# Reefwing-NFC-Card-RevD.net
KiCad netlist of a schematic drawn in EasyEDA
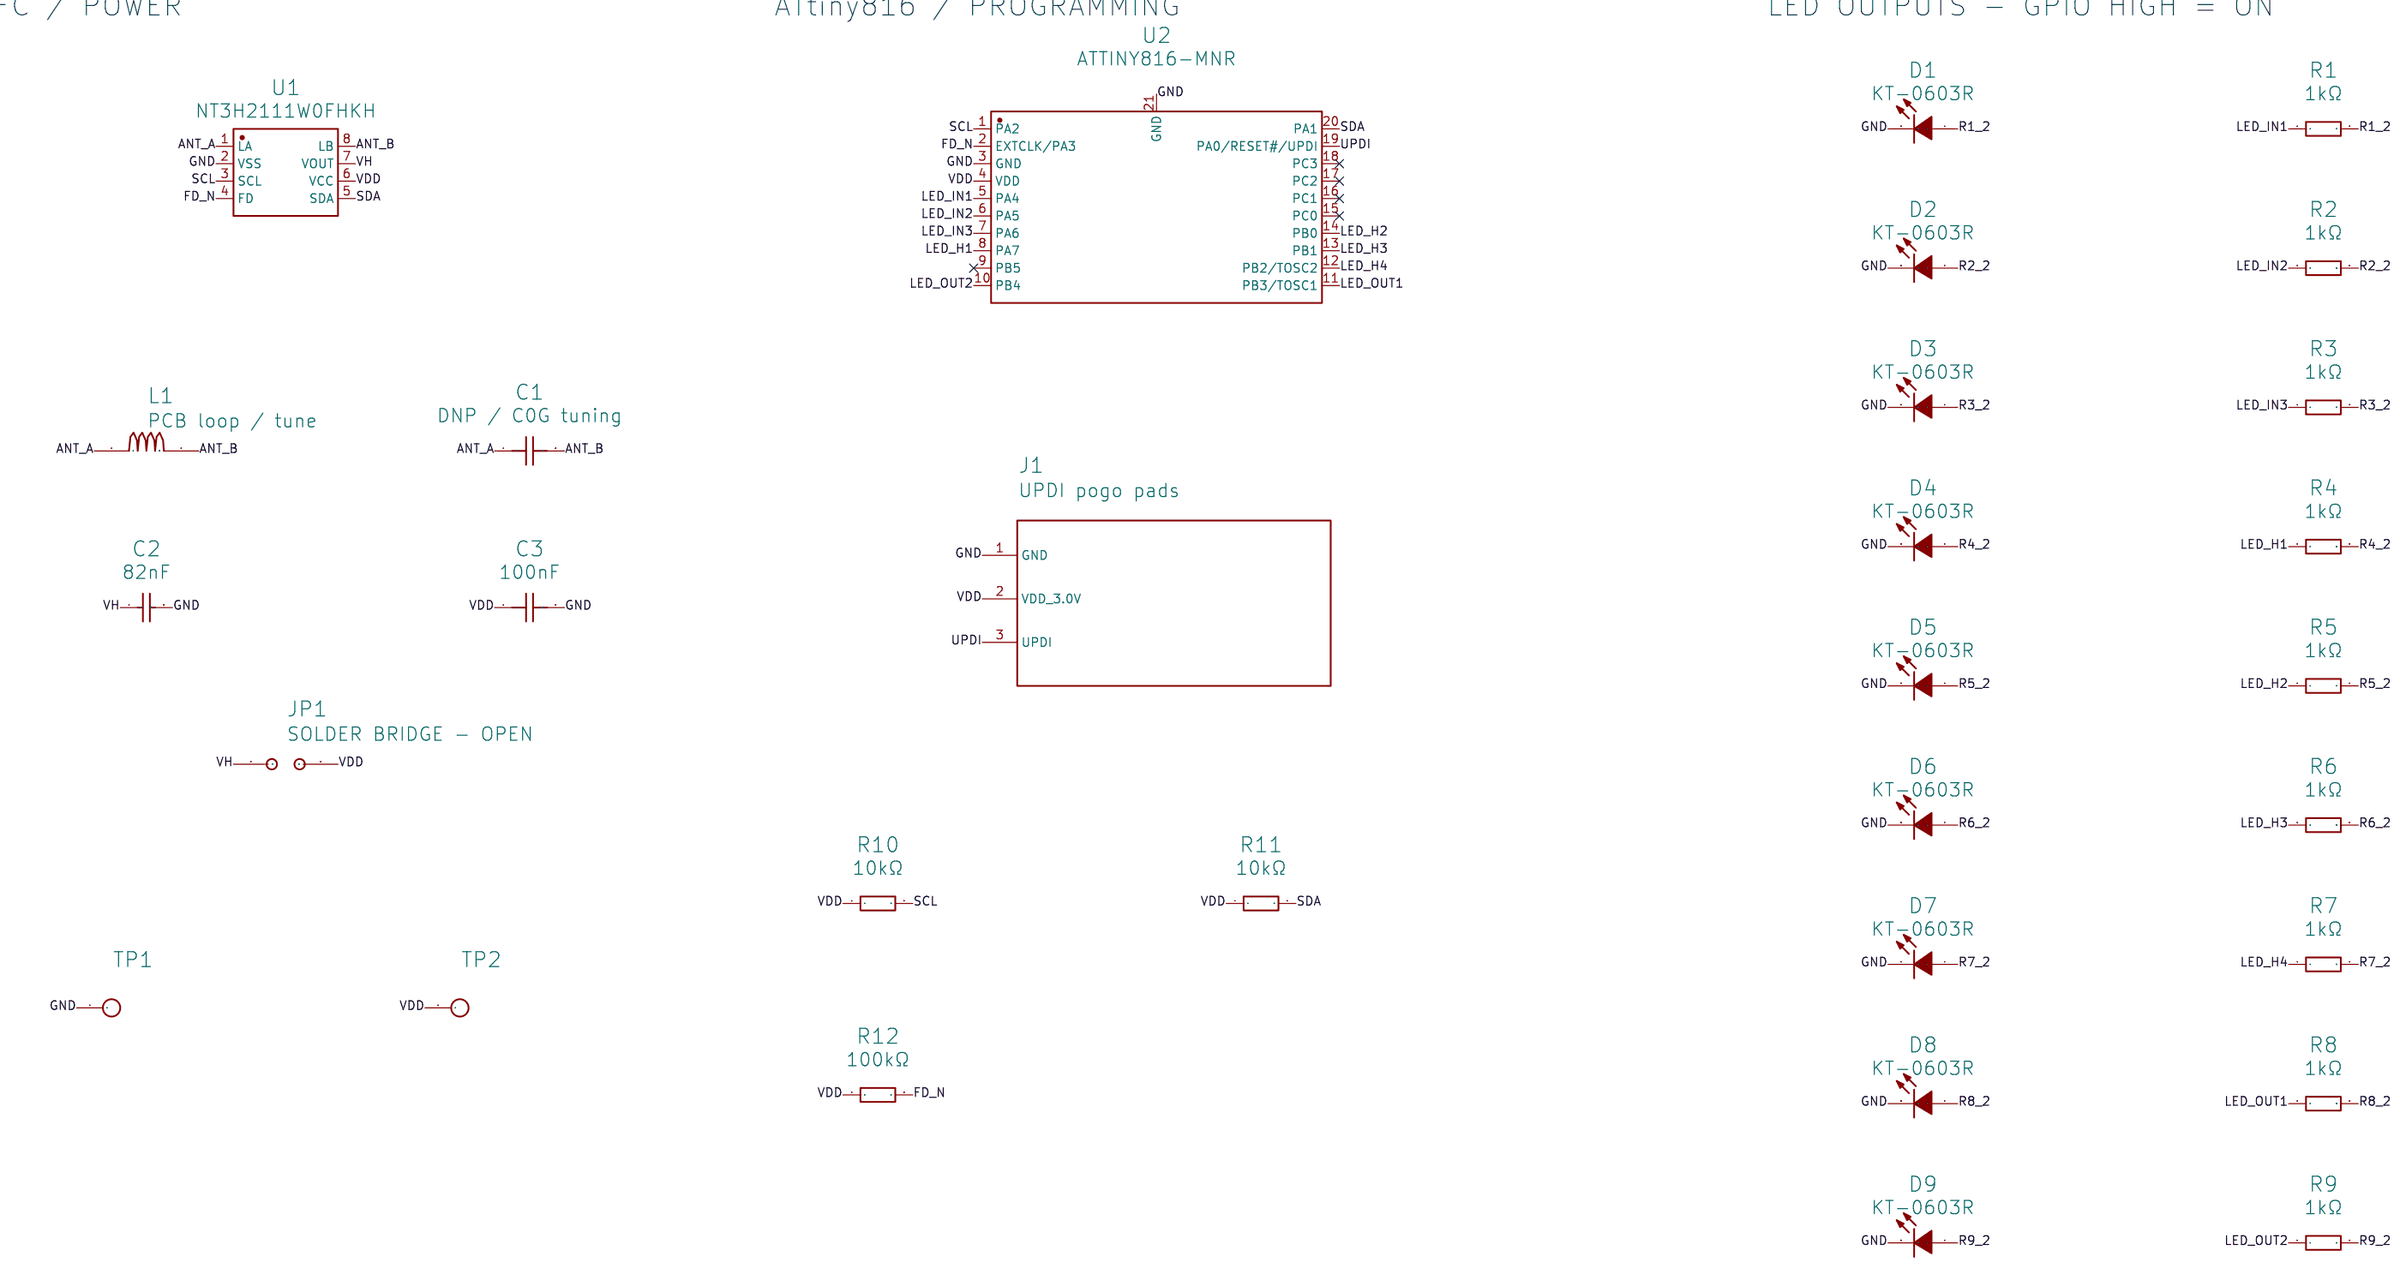
[diagram p0: schematic sheet]

(export (version "E")
  (design (tool "Eeschema 10.0.6"))
  (components
    (comp (ref "C1") (value "DNP / C0G tuning") (libsource (lib "") (part "Unknown_390_370")))
    (comp (ref "C2")
      (value "82nF")
      (fields
        (field (name "Manufacturer Part") "CC0603KRX7R9BB823")
        (field (name "Manufacturer") "YAGEO(国巨)")
      )
      (libsource (lib "") (part "Unknown_170_460"))
    )
    (comp (ref "C3")
      (value "100nF")
      (fields
        (field (name "Manufacturer Part") "CC0603KRX7R9BB104")
        (field (name "Manufacturer") "YAGEO(国巨)")
      )
      (libsource (lib "") (part "Unknown_390_460"))
    )
    (comp (ref "D1")
      (value "KT-0603R")
      (fields (field (name "Manufacturer") "KENTO"))
      (libsource (lib "") (part "Unknown_1190_185"))
    )
    (comp (ref "D2")
      (value "KT-0603R")
      (fields (field (name "Manufacturer") "KENTO"))
      (libsource (lib "") (part "Unknown_1190_265"))
    )
    (comp (ref "D3")
      (value "KT-0603R")
      (fields (field (name "Manufacturer") "KENTO"))
      (libsource (lib "") (part "Unknown_1190_345"))
    )
    (comp (ref "D4")
      (value "KT-0603R")
      (fields (field (name "Manufacturer") "KENTO"))
      (libsource (lib "") (part "Unknown_1190_425"))
    )
    (comp (ref "D5")
      (value "KT-0603R")
      (fields (field (name "Manufacturer") "KENTO"))
      (libsource (lib "") (part "Unknown_1190_505"))
    )
    (comp (ref "D6")
      (value "KT-0603R")
      (fields (field (name "Manufacturer") "KENTO"))
      (libsource (lib "") (part "Unknown_1190_585"))
    )
    (comp (ref "D7")
      (value "KT-0603R")
      (fields (field (name "Manufacturer") "KENTO"))
      (libsource (lib "") (part "Unknown_1190_665"))
    )
    (comp (ref "D8")
      (value "KT-0603R")
      (fields (field (name "Manufacturer") "KENTO"))
      (libsource (lib "") (part "Unknown_1190_745"))
    )
    (comp (ref "D9")
      (value "KT-0603R")
      (fields (field (name "Manufacturer") "KENTO"))
      (libsource (lib "") (part "Unknown_1190_825"))
    )
    (comp (ref "J1") (value "UPDI pogo pads") (libsource (lib "") (part "Unknown_670_410")))
    (comp (ref "JP1") (value "SOLDER BRIDGE - OPEN") (libsource (lib "") (part "Unknown_250_550")))
    (comp (ref "L1") (value "PCB loop / tune") (libsource (lib "") (part "Unknown_170_370")))
    (comp (ref "R1")
      (value "1kΩ")
      (fields
        (field (name "Manufacturer Part") "0603WAF1001T5E")
        (field (name "Manufacturer") "UNI-ROYAL(厚声)")
      )
      (libsource (lib "") (part "Unknown_1420_185"))
    )
    (comp (ref "R2")
      (value "1kΩ")
      (fields
        (field (name "Manufacturer Part") "0603WAF1001T5E")
        (field (name "Manufacturer") "UNI-ROYAL(厚声)")
      )
      (libsource (lib "") (part "Unknown_1420_265"))
    )
    (comp (ref "R3")
      (value "1kΩ")
      (fields
        (field (name "Manufacturer Part") "0603WAF1001T5E")
        (field (name "Manufacturer") "UNI-ROYAL(厚声)")
      )
      (libsource (lib "") (part "Unknown_1420_345"))
    )
    (comp (ref "R4")
      (value "1kΩ")
      (fields
        (field (name "Manufacturer Part") "0603WAF1001T5E")
        (field (name "Manufacturer") "UNI-ROYAL(厚声)")
      )
      (libsource (lib "") (part "Unknown_1420_425"))
    )
    (comp (ref "R5")
      (value "1kΩ")
      (fields
        (field (name "Manufacturer Part") "0603WAF1001T5E")
        (field (name "Manufacturer") "UNI-ROYAL(厚声)")
      )
      (libsource (lib "") (part "Unknown_1420_505"))
    )
    (comp (ref "R6")
      (value "1kΩ")
      (fields
        (field (name "Manufacturer Part") "0603WAF1001T5E")
        (field (name "Manufacturer") "UNI-ROYAL(厚声)")
      )
      (libsource (lib "") (part "Unknown_1420_585"))
    )
    (comp (ref "R7")
      (value "1kΩ")
      (fields
        (field (name "Manufacturer Part") "0603WAF1001T5E")
        (field (name "Manufacturer") "UNI-ROYAL(厚声)")
      )
      (libsource (lib "") (part "Unknown_1420_665"))
    )
    (comp (ref "R8")
      (value "1kΩ")
      (fields
        (field (name "Manufacturer Part") "0603WAF1001T5E")
        (field (name "Manufacturer") "UNI-ROYAL(厚声)")
      )
      (libsource (lib "") (part "Unknown_1420_745"))
    )
    (comp (ref "R9")
      (value "1kΩ")
      (fields
        (field (name "Manufacturer Part") "0603WAF1001T5E")
        (field (name "Manufacturer") "UNI-ROYAL(厚声)")
      )
      (libsource (lib "") (part "Unknown_1420_825"))
    )
    (comp (ref "R10")
      (value "10kΩ")
      (fields
        (field (name "Manufacturer Part") "0603WAF1002T5E")
        (field (name "Manufacturer") "UNI-ROYAL(厚声)")
      )
      (libsource (lib "") (part "Unknown_590_630"))
    )
    (comp (ref "R11")
      (value "10kΩ")
      (fields
        (field (name "Manufacturer Part") "0603WAF1002T5E")
        (field (name "Manufacturer") "UNI-ROYAL(厚声)")
      )
      (libsource (lib "") (part "Unknown_810_630"))
    )
    (comp (ref "R12")
      (value "100kΩ")
      (fields
        (field (name "Manufacturer Part") "0603WAF1003T5E")
        (field (name "Manufacturer") "UNI-ROYAL(厚声)")
      )
      (libsource (lib "") (part "Unknown_590_740"))
    )
    (comp (ref "TP1") (value "TEST PAD") (libsource (lib "") (part "Unknown_150_690")))
    (comp (ref "TP2") (value "TEST PAD") (libsource (lib "") (part "Unknown_350_690")))
    (comp (ref "U1")
      (value "NT3H2111W0FHKH")
      (fields (field (name "Manufacturer") "NXP(恩智浦)"))
      (libsource (lib "") (part "Unknown_250_210"))
    )
    (comp (ref "U2")
      (value "ATTINY816-MNR")
      (fields (field (name "Manufacturer") "MICROCHIP(美国微芯)"))
      (libsource (lib "") (part "Unknown_750_230"))
    )
  )
  (nets
    (net (code "1") (name "/ANT_A") (class "Default")
      (node (ref "C1") (pin "1") (pinfunction "1_1") (pintype "unspecified"))
      (node (ref "L1") (pin "1") (pinfunction "1_1") (pintype "unspecified"))
      (node (ref "U1") (pin "1") (pinfunction "LA_1") (pintype "unspecified"))
    )
    (net (code "2") (name "/ANT_B") (class "Default")
      (node (ref "C1") (pin "2") (pinfunction "2_2") (pintype "unspecified"))
      (node (ref "L1") (pin "2") (pinfunction "2_2") (pintype "unspecified"))
      (node (ref "U1") (pin "8") (pinfunction "LB_8") (pintype "unspecified"))
    )
    (net (code "3") (name "/FD_N") (class "Default")
      (node (ref "R12") (pin "2") (pinfunction "2_2") (pintype "input"))
      (node (ref "U1") (pin "4") (pinfunction "FD_4") (pintype "unspecified"))
      (node (ref "U2") (pin "2") (pinfunction "EXTCLK/PA3_2") (pintype "unspecified"))
    )
    (net (code "4") (name "/GND") (class "Default")
      (node (ref "C2") (pin "2") (pinfunction "2_2") (pintype "input"))
      (node (ref "C3") (pin "2") (pinfunction "2_2") (pintype "unspecified"))
      (node (ref "D1") (pin "2") (pinfunction "K_2") (pintype "unspecified"))
      (node (ref "D2") (pin "2") (pinfunction "K_2") (pintype "unspecified"))
      (node (ref "D3") (pin "2") (pinfunction "K_2") (pintype "unspecified"))
      (node (ref "D4") (pin "2") (pinfunction "K_2") (pintype "unspecified"))
      (node (ref "D5") (pin "2") (pinfunction "K_2") (pintype "unspecified"))
      (node (ref "D6") (pin "2") (pinfunction "K_2") (pintype "unspecified"))
      (node (ref "D7") (pin "2") (pinfunction "K_2") (pintype "unspecified"))
      (node (ref "D8") (pin "2") (pinfunction "K_2") (pintype "unspecified"))
      (node (ref "D9") (pin "2") (pinfunction "K_2") (pintype "unspecified"))
      (node (ref "J1") (pin "1") (pinfunction "GND_1") (pintype "unspecified"))
      (node (ref "TP1") (pin "1") (pinfunction "1_1") (pintype "unspecified"))
      (node (ref "U1") (pin "2") (pinfunction "VSS_2") (pintype "unspecified"))
      (node (ref "U2") (pin "21") (pinfunction "GND_21") (pintype "unspecified"))
      (node (ref "U2") (pin "3") (pinfunction "GND_3") (pintype "unspecified"))
    )
    (net (code "5") (name "/LED_H1") (class "Default")
      (node (ref "R4") (pin "1") (pinfunction "1_1") (pintype "input"))
      (node (ref "U2") (pin "8") (pinfunction "PA7_8") (pintype "unspecified"))
    )
    (net (code "6") (name "/LED_H2") (class "Default")
      (node (ref "R5") (pin "1") (pinfunction "1_1") (pintype "input"))
      (node (ref "U2") (pin "14") (pinfunction "PB0_14") (pintype "unspecified"))
    )
    (net (code "7") (name "/LED_H3") (class "Default")
      (node (ref "R6") (pin "1") (pinfunction "1_1") (pintype "input"))
      (node (ref "U2") (pin "13") (pinfunction "PB1_13") (pintype "unspecified"))
    )
    (net (code "8") (name "/LED_H4") (class "Default")
      (node (ref "R7") (pin "1") (pinfunction "1_1") (pintype "input"))
      (node (ref "U2") (pin "12") (pinfunction "PB2/TOSC2_12") (pintype "unspecified"))
    )
    (net (code "9") (name "/LED_IN1") (class "Default")
      (node (ref "R1") (pin "1") (pinfunction "1_1") (pintype "input"))
      (node (ref "U2") (pin "5") (pinfunction "PA4_5") (pintype "unspecified"))
    )
    (net (code "10") (name "/LED_IN2") (class "Default")
      (node (ref "R2") (pin "1") (pinfunction "1_1") (pintype "input"))
      (node (ref "U2") (pin "6") (pinfunction "PA5_6") (pintype "unspecified"))
    )
    (net (code "11") (name "/LED_IN3") (class "Default")
      (node (ref "R3") (pin "1") (pinfunction "1_1") (pintype "input"))
      (node (ref "U2") (pin "7") (pinfunction "PA6_7") (pintype "unspecified"))
    )
    (net (code "12") (name "/LED_OUT1") (class "Default")
      (node (ref "R8") (pin "1") (pinfunction "1_1") (pintype "input"))
      (node (ref "U2") (pin "11") (pinfunction "PB3/TOSC1_11") (pintype "unspecified"))
    )
    (net (code "13") (name "/LED_OUT2") (class "Default")
      (node (ref "R9") (pin "1") (pinfunction "1_1") (pintype "input"))
      (node (ref "U2") (pin "10") (pinfunction "PB4_10") (pintype "unspecified"))
    )
    (net (code "14") (name "/R1_2") (class "Default")
      (node (ref "D1") (pin "1") (pinfunction "A_1") (pintype "unspecified"))
      (node (ref "R1") (pin "2") (pinfunction "2_2") (pintype "input"))
    )
    (net (code "15") (name "/R2_2") (class "Default")
      (node (ref "D2") (pin "1") (pinfunction "A_1") (pintype "unspecified"))
      (node (ref "R2") (pin "2") (pinfunction "2_2") (pintype "input"))
    )
    (net (code "16") (name "/R3_2") (class "Default")
      (node (ref "D3") (pin "1") (pinfunction "A_1") (pintype "unspecified"))
      (node (ref "R3") (pin "2") (pinfunction "2_2") (pintype "input"))
    )
    (net (code "17") (name "/R4_2") (class "Default")
      (node (ref "D4") (pin "1") (pinfunction "A_1") (pintype "unspecified"))
      (node (ref "R4") (pin "2") (pinfunction "2_2") (pintype "input"))
    )
    (net (code "18") (name "/R5_2") (class "Default")
      (node (ref "D5") (pin "1") (pinfunction "A_1") (pintype "unspecified"))
      (node (ref "R5") (pin "2") (pinfunction "2_2") (pintype "input"))
    )
    (net (code "19") (name "/R6_2") (class "Default")
      (node (ref "D6") (pin "1") (pinfunction "A_1") (pintype "unspecified"))
      (node (ref "R6") (pin "2") (pinfunction "2_2") (pintype "input"))
    )
    (net (code "20") (name "/R7_2") (class "Default")
      (node (ref "D7") (pin "1") (pinfunction "A_1") (pintype "unspecified"))
      (node (ref "R7") (pin "2") (pinfunction "2_2") (pintype "input"))
    )
    (net (code "21") (name "/R8_2") (class "Default")
      (node (ref "D8") (pin "1") (pinfunction "A_1") (pintype "unspecified"))
      (node (ref "R8") (pin "2") (pinfunction "2_2") (pintype "input"))
    )
    (net (code "22") (name "/R9_2") (class "Default")
      (node (ref "D9") (pin "1") (pinfunction "A_1") (pintype "unspecified"))
      (node (ref "R9") (pin "2") (pinfunction "2_2") (pintype "input"))
    )
    (net (code "23") (name "/SCL") (class "Default")
      (node (ref "R10") (pin "2") (pinfunction "2_2") (pintype "input"))
      (node (ref "U1") (pin "3") (pinfunction "SCL_3") (pintype "unspecified"))
      (node (ref "U2") (pin "1") (pinfunction "PA2_1") (pintype "unspecified"))
    )
    (net (code "24") (name "/SDA") (class "Default")
      (node (ref "R11") (pin "2") (pinfunction "2_2") (pintype "input"))
      (node (ref "U1") (pin "5") (pinfunction "SDA_5") (pintype "unspecified"))
      (node (ref "U2") (pin "20") (pinfunction "PA1_20") (pintype "unspecified"))
    )
    (net (code "25") (name "/UPDI") (class "Default")
      (node (ref "J1") (pin "3") (pinfunction "UPDI_3") (pintype "unspecified"))
      (node (ref "U2") (pin "19") (pinfunction "PA0/RESET#/UPDI_19") (pintype "unspecified"))
    )
    (net (code "26") (name "/VDD") (class "Default")
      (node (ref "C3") (pin "1") (pinfunction "1_1") (pintype "unspecified"))
      (node (ref "J1") (pin "2") (pinfunction "VDD_3.0V_2") (pintype "unspecified"))
      (node (ref "JP1") (pin "2") (pinfunction "2_2") (pintype "unspecified"))
      (node (ref "R10") (pin "1") (pinfunction "1_1") (pintype "input"))
      (node (ref "R11") (pin "1") (pinfunction "1_1") (pintype "input"))
      (node (ref "R12") (pin "1") (pinfunction "1_1") (pintype "input"))
      (node (ref "TP2") (pin "1") (pinfunction "1_1") (pintype "unspecified"))
      (node (ref "U1") (pin "6") (pinfunction "VCC_6") (pintype "unspecified"))
      (node (ref "U2") (pin "4") (pinfunction "VDD_4") (pintype "unspecified"))
    )
    (net (code "27") (name "/VH") (class "Default")
      (node (ref "C2") (pin "1") (pinfunction "1_1") (pintype "input"))
      (node (ref "JP1") (pin "1") (pinfunction "1_1") (pintype "unspecified"))
      (node (ref "U1") (pin "7") (pinfunction "VOUT_7") (pintype "unspecified"))
    )
    (net (code "28") (name "unconnected-(U2-PB5-Pad9)") (class "Default")
      (node (ref "U2") (pin "9") (pinfunction "PB5_9") (pintype "unspecified+no_connect"))
    )
    (net (code "29") (name "unconnected-(U2-PC0-Pad15)") (class "Default")
      (node (ref "U2") (pin "15") (pinfunction "PC0_15") (pintype "unspecified+no_connect"))
    )
    (net (code "30") (name "unconnected-(U2-PC1-Pad16)") (class "Default")
      (node (ref "U2") (pin "16") (pinfunction "PC1_16") (pintype "unspecified+no_connect"))
    )
    (net (code "31") (name "unconnected-(U2-PC2-Pad17)") (class "Default")
      (node (ref "U2") (pin "17") (pinfunction "PC2_17") (pintype "unspecified+no_connect"))
    )
    (net (code "32") (name "unconnected-(U2-PC3-Pad18)") (class "Default")
      (node (ref "U2") (pin "18") (pinfunction "PC3_18") (pintype "unspecified+no_connect"))
    )
  )
)
